# cociclo_03.net
KiCad netlist of a schematic drawn in EAGLE
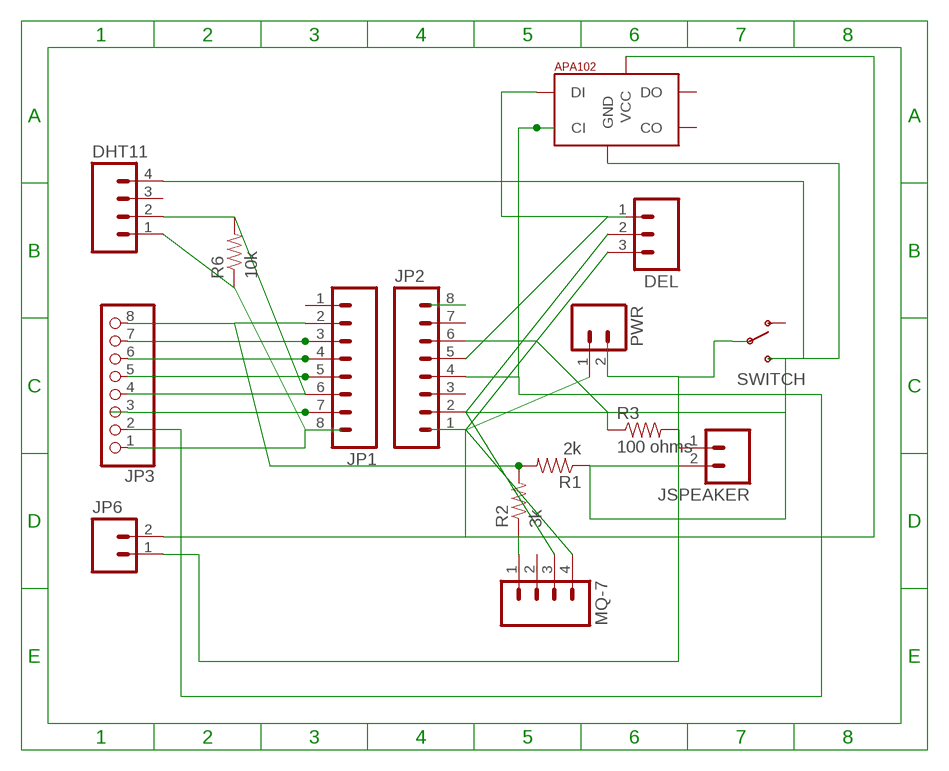
[diagram p0: schematic, sheet 1]

(export (version "E")
  (design (tool "Eeschema 10.0.6"))
  (components
    (comp (ref "DEL")
      (value "M03PTH")
      (footprint "eagle-import:1X03")
      (libsource (lib "eagle-import") (part "M03PTH"))
    )
    (comp (ref "DHT11")
      (value "M04PTH")
      (footprint "eagle-import:1X04")
      (libsource (lib "eagle-import") (part "M04PTH"))
    )
    (comp (ref "JP1")
      (value "M08")
      (footprint "eagle-import:1X08_ROUND")
      (libsource (lib "eagle-import") (part "M08"))
    )
    (comp (ref "JP2")
      (value "M08")
      (footprint "eagle-import:1X08_ROUND")
      (libsource (lib "eagle-import") (part "M08"))
    )
    (comp (ref "JP3")
      (value "PINHD-1X8-3.5MM")
      (footprint "eagle-import:1X08-3.5MM")
      (libsource (lib "eagle-import") (part "PINHD-1X8-3.5MM"))
    )
    (comp (ref "JP6")
      (value "M023.5MM")
      (footprint "eagle-import:SCREWTERMINAL-3.5MM-2")
      (libsource (lib "eagle-import") (part "M023.5MM"))
    )
    (comp (ref "JSPEAKER")
      (value "M02PTH")
      (footprint "eagle-import:1X02")
      (libsource (lib "eagle-import") (part "M02PTH"))
    )
    (comp (ref "LED")
      (value "APA1025050")
      (footprint "eagle-import:APA102_5050")
      (libsource (lib "eagle-import") (part "APA1025050"))
    )
    (comp (ref "MQ-7")
      (value "M04PTH")
      (footprint "eagle-import:1X04")
      (libsource (lib "eagle-import") (part "M04PTH"))
    )
    (comp (ref "PWR")
      (value "M02LOCK_LONGPADS")
      (footprint "eagle-import:1X02_LOCK_LONGPADS")
      (libsource (lib "eagle-import") (part "M02LOCK_LONGPADS"))
    )
    (comp (ref "R1")
      (value "2k")
      (footprint "eagle-import:1206")
      (libsource (lib "eagle-import") (part "RESISTOR1206"))
    )
    (comp (ref "R2")
      (value "3k")
      (footprint "eagle-import:1206")
      (libsource (lib "eagle-import") (part "RESISTOR1206"))
    )
    (comp (ref "R3")
      (value "100 ohms")
      (footprint "eagle-import:1206")
      (libsource (lib "eagle-import") (part "RESISTOR1206"))
    )
    (comp (ref "R6")
      (value "10k")
      (footprint "eagle-import:1206")
      (libsource (lib "eagle-import") (part "RESISTOR1206"))
    )
    (comp (ref "SWITCH")
      (value "SWITCH-SPDTKIT")
      (footprint "eagle-import:SWITCH-SPDT_KIT")
      (libsource (lib "eagle-import") (part "SWITCH-SPDTKIT"))
    )
  )
  (nets
    (net (code "1") (name "Net-(DHT11-Pad1)") (class "Default")
      (node (ref "DHT11") (pin "1") (pinfunction "1_1") (pintype "passive"))
      (node (ref "JP1") (pin "8") (pinfunction "8_8") (pintype "passive"))
      (node (ref "JP3") (pin "1") (pinfunction "1_1") (pintype "passive"))
      (node (ref "R6") (pin "1") (pinfunction "1_1") (pintype "passive"))
    )
    (net (code "2") (name "Net-(DHT11-Pad2)") (class "Default")
      (node (ref "DHT11") (pin "2") (pinfunction "2_2") (pintype "passive"))
      (node (ref "JP1") (pin "6") (pinfunction "6_6") (pintype "passive"))
      (node (ref "JP3") (pin "4") (pinfunction "4_4") (pintype "passive"))
      (node (ref "R6") (pin "2") (pinfunction "2_2") (pintype "passive"))
    )
    (net (code "3") (name "Net-(JP1-Pad2)") (class "Default")
      (node (ref "JP1") (pin "2") (pinfunction "2_2") (pintype "passive"))
      (node (ref "JP3") (pin "8") (pinfunction "8_8") (pintype "passive"))
      (node (ref "R1") (pin "2") (pinfunction "2_2") (pintype "passive"))
      (node (ref "R2") (pin "2") (pinfunction "2_2") (pintype "passive"))
    )
    (net (code "4") (name "Net-(JP1-Pad3)") (class "Default")
      (node (ref "JP1") (pin "3") (pinfunction "3_3") (pintype "passive"))
      (node (ref "JP3") (pin "7") (pinfunction "7_7") (pintype "passive"))
    )
    (net (code "5") (name "Net-(JP1-Pad4)") (class "Default")
      (node (ref "JP1") (pin "4") (pinfunction "4_4") (pintype "passive"))
      (node (ref "JP3") (pin "6") (pinfunction "6_6") (pintype "passive"))
    )
    (net (code "6") (name "Net-(JP1-Pad5)") (class "Default")
      (node (ref "JP1") (pin "5") (pinfunction "5_5") (pintype "passive"))
      (node (ref "JP3") (pin "5") (pinfunction "5_5") (pintype "passive"))
    )
    (net (code "7") (name "Net-(JP1-Pad7)") (class "Default")
      (node (ref "JP1") (pin "7") (pinfunction "7_7") (pintype "passive"))
      (node (ref "JP3") (pin "3") (pinfunction "3_3") (pintype "passive"))
    )
    (net (code "8") (name "Net-(JP2-Pad6)") (class "Default")
      (node (ref "JP2") (pin "6") (pinfunction "6_6") (pintype "passive"))
      (node (ref "R3") (pin "1") (pinfunction "1_1") (pintype "passive"))
    )
    (net (code "9") (name "Net-(JSPEAKER-Pad1)") (class "Default")
      (node (ref "JSPEAKER") (pin "1") (pinfunction "1_1") (pintype "passive"))
      (node (ref "R3") (pin "2") (pinfunction "2_2") (pintype "passive"))
    )
    (net (code "10") (name "Net-(LED-CI)") (class "Default")
      (node (ref "JP2") (pin "4") (pinfunction "4_4") (pintype "passive"))
      (node (ref "JP3") (pin "2") (pinfunction "2_2") (pintype "passive"))
      (node (ref "LED") (pin "5") (pinfunction "CI_5") (pintype "bidirectional"))
    )
    (net (code "11") (name "Net-(LED-DI)") (class "Default")
      (node (ref "DEL") (pin "1") (pinfunction "1_1") (pintype "passive"))
      (node (ref "JP2") (pin "5") (pinfunction "5_5") (pintype "passive"))
      (node (ref "LED") (pin "4") (pinfunction "DI_4") (pintype "bidirectional"))
    )
    (net (code "12") (name "Net-(LED-GND)") (class "Default")
      (node (ref "DEL") (pin "2") (pinfunction "2_2") (pintype "passive"))
      (node (ref "DHT11") (pin "4") (pinfunction "4_4") (pintype "passive"))
      (node (ref "JP2") (pin "2") (pinfunction "2_2") (pintype "passive"))
      (node (ref "JSPEAKER") (pin "2") (pinfunction "2_2") (pintype "passive"))
      (node (ref "LED") (pin "6") (pinfunction "GND_6") (pintype "bidirectional"))
      (node (ref "MQ-7") (pin "3") (pinfunction "3_3") (pintype "passive"))
      (node (ref "R1") (pin "1") (pinfunction "1_1") (pintype "passive"))
      (node (ref "SWITCH") (pin "3") (pinfunction "S_3") (pintype "passive"))
    )
    (net (code "13") (name "Net-(LED-VCC)") (class "Default")
      (node (ref "DEL") (pin "3") (pinfunction "3_3") (pintype "passive"))
      (node (ref "JP2") (pin "1") (pinfunction "1_1") (pintype "passive"))
      (node (ref "JP6") (pin "2") (pinfunction "2_2") (pintype "passive"))
      (node (ref "LED") (pin "1") (pinfunction "VCC_1") (pintype "bidirectional"))
      (node (ref "MQ-7") (pin "4") (pinfunction "4_4") (pintype "passive"))
      (node (ref "PWR") (pin "1") (pinfunction "1_1") (pintype "passive"))
    )
    (net (code "14") (name "Net-(MQ-7-Pad1)") (class "Default")
      (node (ref "MQ-7") (pin "1") (pinfunction "1_1") (pintype "passive"))
      (node (ref "R2") (pin "1") (pinfunction "1_1") (pintype "passive"))
    )
    (net (code "15") (name "Net-(SWITCH-P)") (class "Default")
      (node (ref "JP6") (pin "1") (pinfunction "1_1") (pintype "passive"))
      (node (ref "PWR") (pin "2") (pinfunction "2_2") (pintype "passive"))
      (node (ref "SWITCH") (pin "2") (pinfunction "P_2") (pintype "passive"))
    )
    (net (code "16") (name "unconnected-(DHT11-Pad3)") (class "Default")
      (node (ref "DHT11") (pin "3") (pinfunction "3_3") (pintype "passive"))
    )
    (net (code "17") (name "unconnected-(JP1-Pad1)") (class "Default")
      (node (ref "JP1") (pin "1") (pinfunction "1_1") (pintype "passive"))
    )
    (net (code "18") (name "unconnected-(JP2-Pad3)") (class "Default")
      (node (ref "JP2") (pin "3") (pinfunction "3_3") (pintype "passive"))
    )
    (net (code "19") (name "unconnected-(JP2-Pad7)") (class "Default")
      (node (ref "JP2") (pin "7") (pinfunction "7_7") (pintype "passive"))
    )
    (net (code "20") (name "unconnected-(JP2-Pad8)") (class "Default")
      (node (ref "JP2") (pin "8") (pinfunction "8_8") (pintype "passive"))
    )
    (net (code "21") (name "unconnected-(LED-CO-Pad2)") (class "Default")
      (node (ref "LED") (pin "2") (pinfunction "CO_2") (pintype "bidirectional"))
    )
    (net (code "22") (name "unconnected-(LED-DO-Pad3)") (class "Default")
      (node (ref "LED") (pin "3") (pinfunction "DO_3") (pintype "bidirectional"))
    )
    (net (code "23") (name "unconnected-(MQ-7-Pad2)") (class "Default")
      (node (ref "MQ-7") (pin "2") (pinfunction "2_2") (pintype "passive"))
    )
    (net (code "24") (name "unconnected-(SWITCH-O-Pad1)") (class "Default")
      (node (ref "SWITCH") (pin "1") (pinfunction "O_1") (pintype "passive"))
    )
  )
)
